# axiom_beta_center_solder_on_v0_1.net
KiCad netlist of a schematic drawn in EAGLE
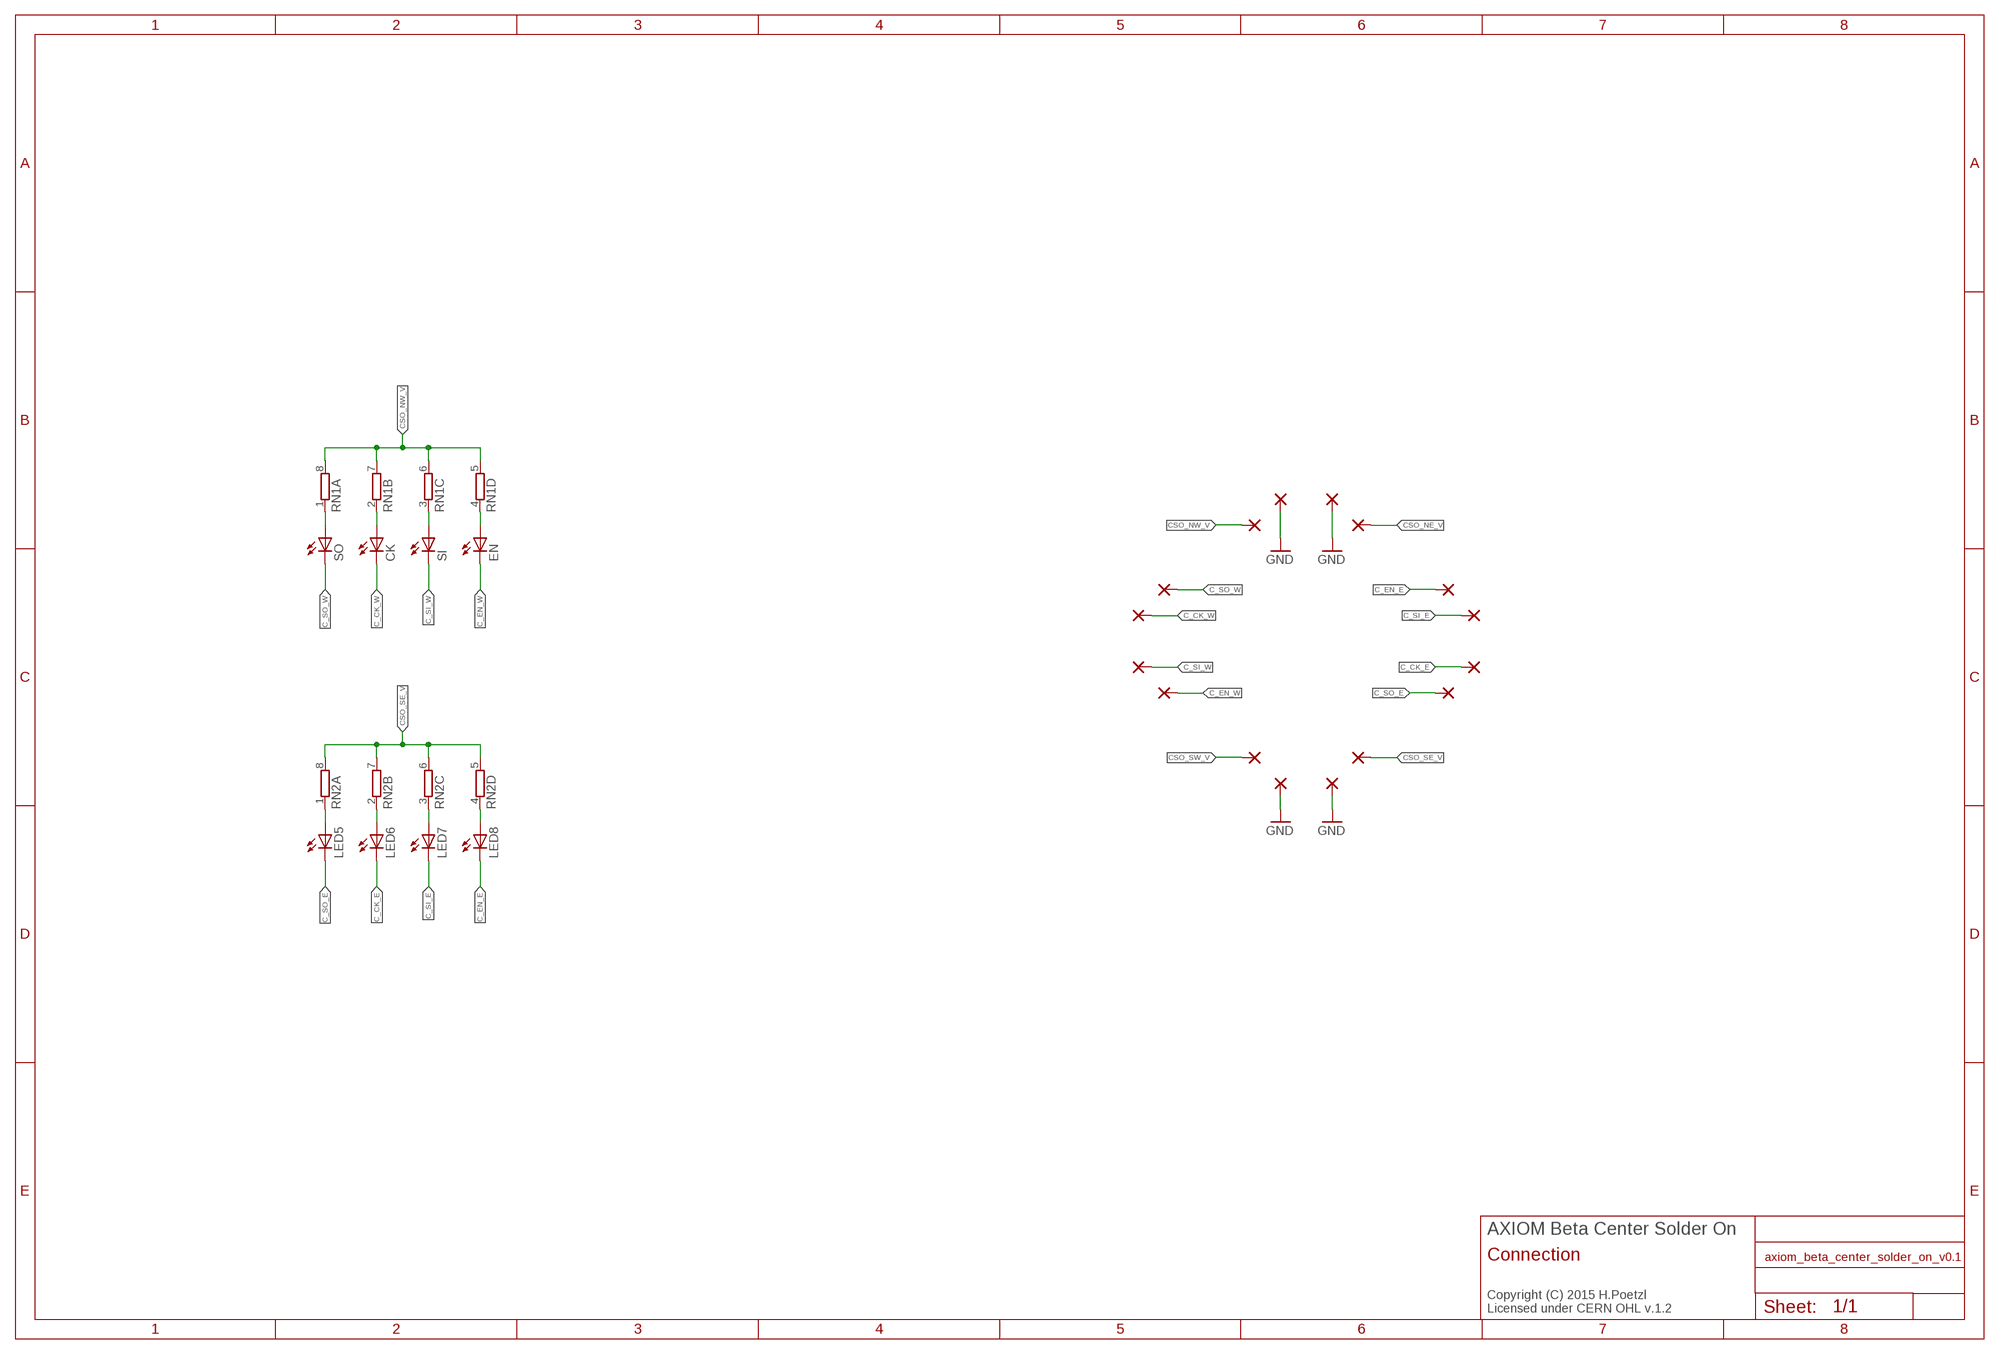
[diagram p0: schematic, sheet 1]

(export (version "E")
  (design (tool "Eeschema 10.0.6"))
  (components
    (comp (ref "CK")
      (value "LEDCHIPLED_0603")
      (footprint "eagle-import:CHIPLED_0603")
      (libsource (lib "eagle-import") (part "LEDCHIPLED_0603"))
    )
    (comp (ref "EN")
      (value "LEDCHIPLED_0603")
      (footprint "eagle-import:CHIPLED_0603")
      (libsource (lib "eagle-import") (part "LEDCHIPLED_0603"))
    )
    (comp (ref "LED5")
      (value "LEDCHIPLED_0603")
      (footprint "eagle-import:CHIPLED_0603")
      (libsource (lib "eagle-import") (part "LEDCHIPLED_0603"))
    )
    (comp (ref "LED6")
      (value "LEDCHIPLED_0603")
      (footprint "eagle-import:CHIPLED_0603")
      (libsource (lib "eagle-import") (part "LEDCHIPLED_0603"))
    )
    (comp (ref "LED7")
      (value "LEDCHIPLED_0603")
      (footprint "eagle-import:CHIPLED_0603")
      (libsource (lib "eagle-import") (part "LEDCHIPLED_0603"))
    )
    (comp (ref "LED8")
      (value "LEDCHIPLED_0603")
      (footprint "eagle-import:CHIPLED_0603")
      (libsource (lib "eagle-import") (part "LEDCHIPLED_0603"))
    )
    (comp (ref "RN1")
      (value "4R-NCAT16")
      (footprint "eagle-import:CAT16")
      (libsource (lib "eagle-import") (part "4R-NCAT16"))
    )
    (comp (ref "RN2")
      (value "4R-NCAT16")
      (footprint "eagle-import:CAT16")
      (libsource (lib "eagle-import") (part "4R-NCAT16"))
    )
    (comp (ref "SI")
      (value "LEDCHIPLED_0603")
      (footprint "eagle-import:CHIPLED_0603")
      (libsource (lib "eagle-import") (part "LEDCHIPLED_0603"))
    )
    (comp (ref "SO")
      (value "LEDCHIPLED_0603")
      (footprint "eagle-import:CHIPLED_0603")
      (libsource (lib "eagle-import") (part "LEDCHIPLED_0603"))
    )
    (comp (ref "U$1")
      (value "PINPAD2.00MM")
      (footprint "eagle-import:1.4_0.8")
      (libsource (lib "eagle-import") (part "PINPAD2.00MM"))
    )
    (comp (ref "U$2")
      (value "PINPAD2.00MM")
      (footprint "eagle-import:1.4_0.8")
      (libsource (lib "eagle-import") (part "PINPAD2.00MM"))
    )
    (comp (ref "U$3")
      (value "PINPAD2.00MM")
      (footprint "eagle-import:1.4_0.8")
      (libsource (lib "eagle-import") (part "PINPAD2.00MM"))
    )
    (comp (ref "U$4")
      (value "PINPAD2.00MM")
      (footprint "eagle-import:1.4_0.8")
      (libsource (lib "eagle-import") (part "PINPAD2.00MM"))
    )
    (comp (ref "U$5")
      (value "PINPAD2.00MM")
      (footprint "eagle-import:1.4_0.8")
      (libsource (lib "eagle-import") (part "PINPAD2.00MM"))
    )
    (comp (ref "U$6")
      (value "PINPAD2.00MM")
      (footprint "eagle-import:1.4_0.8")
      (libsource (lib "eagle-import") (part "PINPAD2.00MM"))
    )
    (comp (ref "U$11")
      (value "PINPAD2.00MM")
      (footprint "eagle-import:1.4_0.8")
      (libsource (lib "eagle-import") (part "PINPAD2.00MM"))
    )
    (comp (ref "U$14")
      (value "PINPAD2.00MM")
      (footprint "eagle-import:1.4_0.8")
      (libsource (lib "eagle-import") (part "PINPAD2.00MM"))
    )
    (comp (ref "U$15")
      (value "PINPAD2.00MM")
      (footprint "eagle-import:1.4_0.8")
      (libsource (lib "eagle-import") (part "PINPAD2.00MM"))
    )
    (comp (ref "U$16")
      (value "PINPAD2.00MM")
      (footprint "eagle-import:1.4_0.8")
      (libsource (lib "eagle-import") (part "PINPAD2.00MM"))
    )
    (comp (ref "U$17")
      (value "PINPAD2.00MM")
      (footprint "eagle-import:1.4_0.8")
      (libsource (lib "eagle-import") (part "PINPAD2.00MM"))
    )
    (comp (ref "U$18")
      (value "PINPAD2.00MM")
      (footprint "eagle-import:1.4_0.8")
      (libsource (lib "eagle-import") (part "PINPAD2.00MM"))
    )
    (comp (ref "U$19")
      (value "PINPAD2.00MM")
      (footprint "eagle-import:1.4_0.8")
      (libsource (lib "eagle-import") (part "PINPAD2.00MM"))
    )
    (comp (ref "U$20")
      (value "PINPAD2.00MM")
      (footprint "eagle-import:1.4_0.8")
      (libsource (lib "eagle-import") (part "PINPAD2.00MM"))
    )
    (comp (ref "U$21")
      (value "PINPAD2.00MM")
      (footprint "eagle-import:1.4_0.8")
      (libsource (lib "eagle-import") (part "PINPAD2.00MM"))
    )
    (comp (ref "U$22")
      (value "PINPAD2.00MM")
      (footprint "eagle-import:1.4_0.8")
      (libsource (lib "eagle-import") (part "PINPAD2.00MM"))
    )
  )
  (nets
    (net (code "1") (name "CSO_NE_V") (class "Default")
      (node (ref "U$19") (pin "1") (pinfunction "P_1") (pintype "passive"))
    )
    (net (code "2") (name "CSO_NW_V") (class "Default")
      (node (ref "RN1") (pin "5") (pinfunction "2_5") (pintype "passive"))
      (node (ref "RN1") (pin "6") (pinfunction "2_6") (pintype "passive"))
      (node (ref "RN1") (pin "7") (pinfunction "2_7") (pintype "passive"))
      (node (ref "RN1") (pin "8") (pinfunction "2_8") (pintype "passive"))
      (node (ref "U$18") (pin "1") (pinfunction "P_1") (pintype "passive"))
    )
    (net (code "3") (name "CSO_SE_V") (class "Default")
      (node (ref "RN2") (pin "5") (pinfunction "2_5") (pintype "passive"))
      (node (ref "RN2") (pin "6") (pinfunction "2_6") (pintype "passive"))
      (node (ref "RN2") (pin "7") (pinfunction "2_7") (pintype "passive"))
      (node (ref "RN2") (pin "8") (pinfunction "2_8") (pintype "passive"))
      (node (ref "U$21") (pin "1") (pinfunction "P_1") (pintype "passive"))
    )
    (net (code "4") (name "CSO_SW_V") (class "Default")
      (node (ref "U$22") (pin "1") (pinfunction "P_1") (pintype "passive"))
    )
    (net (code "5") (name "C_CK_E") (class "Default")
      (node (ref "LED6") (pin "C") (pinfunction "C_C") (pintype "passive"))
      (node (ref "U$14") (pin "1") (pinfunction "P_1") (pintype "passive"))
    )
    (net (code "6") (name "C_CK_W") (class "Default")
      (node (ref "CK") (pin "C") (pinfunction "C_C") (pintype "passive"))
      (node (ref "U$1") (pin "1") (pinfunction "P_1") (pintype "passive"))
    )
    (net (code "7") (name "C_EN_E") (class "Default")
      (node (ref "LED8") (pin "C") (pinfunction "C_C") (pintype "passive"))
      (node (ref "U$3") (pin "1") (pinfunction "P_1") (pintype "passive"))
    )
    (net (code "8") (name "C_EN_W") (class "Default")
      (node (ref "EN") (pin "C") (pinfunction "C_C") (pintype "passive"))
      (node (ref "U$4") (pin "1") (pinfunction "P_1") (pintype "passive"))
    )
    (net (code "9") (name "C_SI_E") (class "Default")
      (node (ref "LED7") (pin "C") (pinfunction "C_C") (pintype "passive"))
      (node (ref "U$15") (pin "1") (pinfunction "P_1") (pintype "passive"))
    )
    (net (code "10") (name "C_SI_W") (class "Default")
      (node (ref "SI") (pin "C") (pinfunction "C_C") (pintype "passive"))
      (node (ref "U$2") (pin "1") (pinfunction "P_1") (pintype "passive"))
    )
    (net (code "11") (name "C_SO_E") (class "Default")
      (node (ref "LED5") (pin "C") (pinfunction "C_C") (pintype "passive"))
      (node (ref "U$16") (pin "1") (pinfunction "P_1") (pintype "passive"))
    )
    (net (code "12") (name "C_SO_W") (class "Default")
      (node (ref "SO") (pin "C") (pinfunction "C_C") (pintype "passive"))
      (node (ref "U$11") (pin "1") (pinfunction "P_1") (pintype "passive"))
    )
    (net (code "13") (name "GND") (class "Default")
      (node (ref "U$17") (pin "1") (pinfunction "P_1") (pintype "passive"))
      (node (ref "U$20") (pin "1") (pinfunction "P_1") (pintype "passive"))
      (node (ref "U$5") (pin "1") (pinfunction "P_1") (pintype "passive"))
      (node (ref "U$6") (pin "1") (pinfunction "P_1") (pintype "passive"))
    )
    (net (code "14") (name "Net-(LED5-PadA)") (class "Default")
      (node (ref "LED5") (pin "A") (pinfunction "A_A") (pintype "passive"))
      (node (ref "RN2") (pin "1") (pinfunction "1_1") (pintype "passive"))
    )
    (net (code "15") (name "Net-(RN1-Pad1)") (class "Default")
      (node (ref "RN1") (pin "1") (pinfunction "1_1") (pintype "passive"))
      (node (ref "SO") (pin "A") (pinfunction "A_A") (pintype "passive"))
    )
    (net (code "16") (name "Net-(RN1B-1)") (class "Default")
      (node (ref "CK") (pin "A") (pinfunction "A_A") (pintype "passive"))
      (node (ref "RN1") (pin "2") (pinfunction "1_2") (pintype "passive"))
    )
    (net (code "17") (name "Net-(RN1C-1)") (class "Default")
      (node (ref "RN1") (pin "3") (pinfunction "1_3") (pintype "passive"))
      (node (ref "SI") (pin "A") (pinfunction "A_A") (pintype "passive"))
    )
    (net (code "18") (name "Net-(RN1D-1)") (class "Default")
      (node (ref "EN") (pin "A") (pinfunction "A_A") (pintype "passive"))
      (node (ref "RN1") (pin "4") (pinfunction "1_4") (pintype "passive"))
    )
    (net (code "19") (name "Net-(RN2B-1)") (class "Default")
      (node (ref "LED6") (pin "A") (pinfunction "A_A") (pintype "passive"))
      (node (ref "RN2") (pin "2") (pinfunction "1_2") (pintype "passive"))
    )
    (net (code "20") (name "Net-(RN2C-1)") (class "Default")
      (node (ref "LED7") (pin "A") (pinfunction "A_A") (pintype "passive"))
      (node (ref "RN2") (pin "3") (pinfunction "1_3") (pintype "passive"))
    )
    (net (code "21") (name "Net-(RN2D-1)") (class "Default")
      (node (ref "LED8") (pin "A") (pinfunction "A_A") (pintype "passive"))
      (node (ref "RN2") (pin "4") (pinfunction "1_4") (pintype "passive"))
    )
  )
)
